# Gauge_DAC_v2.net
KiCad netlist of a schematic drawn in EAGLE
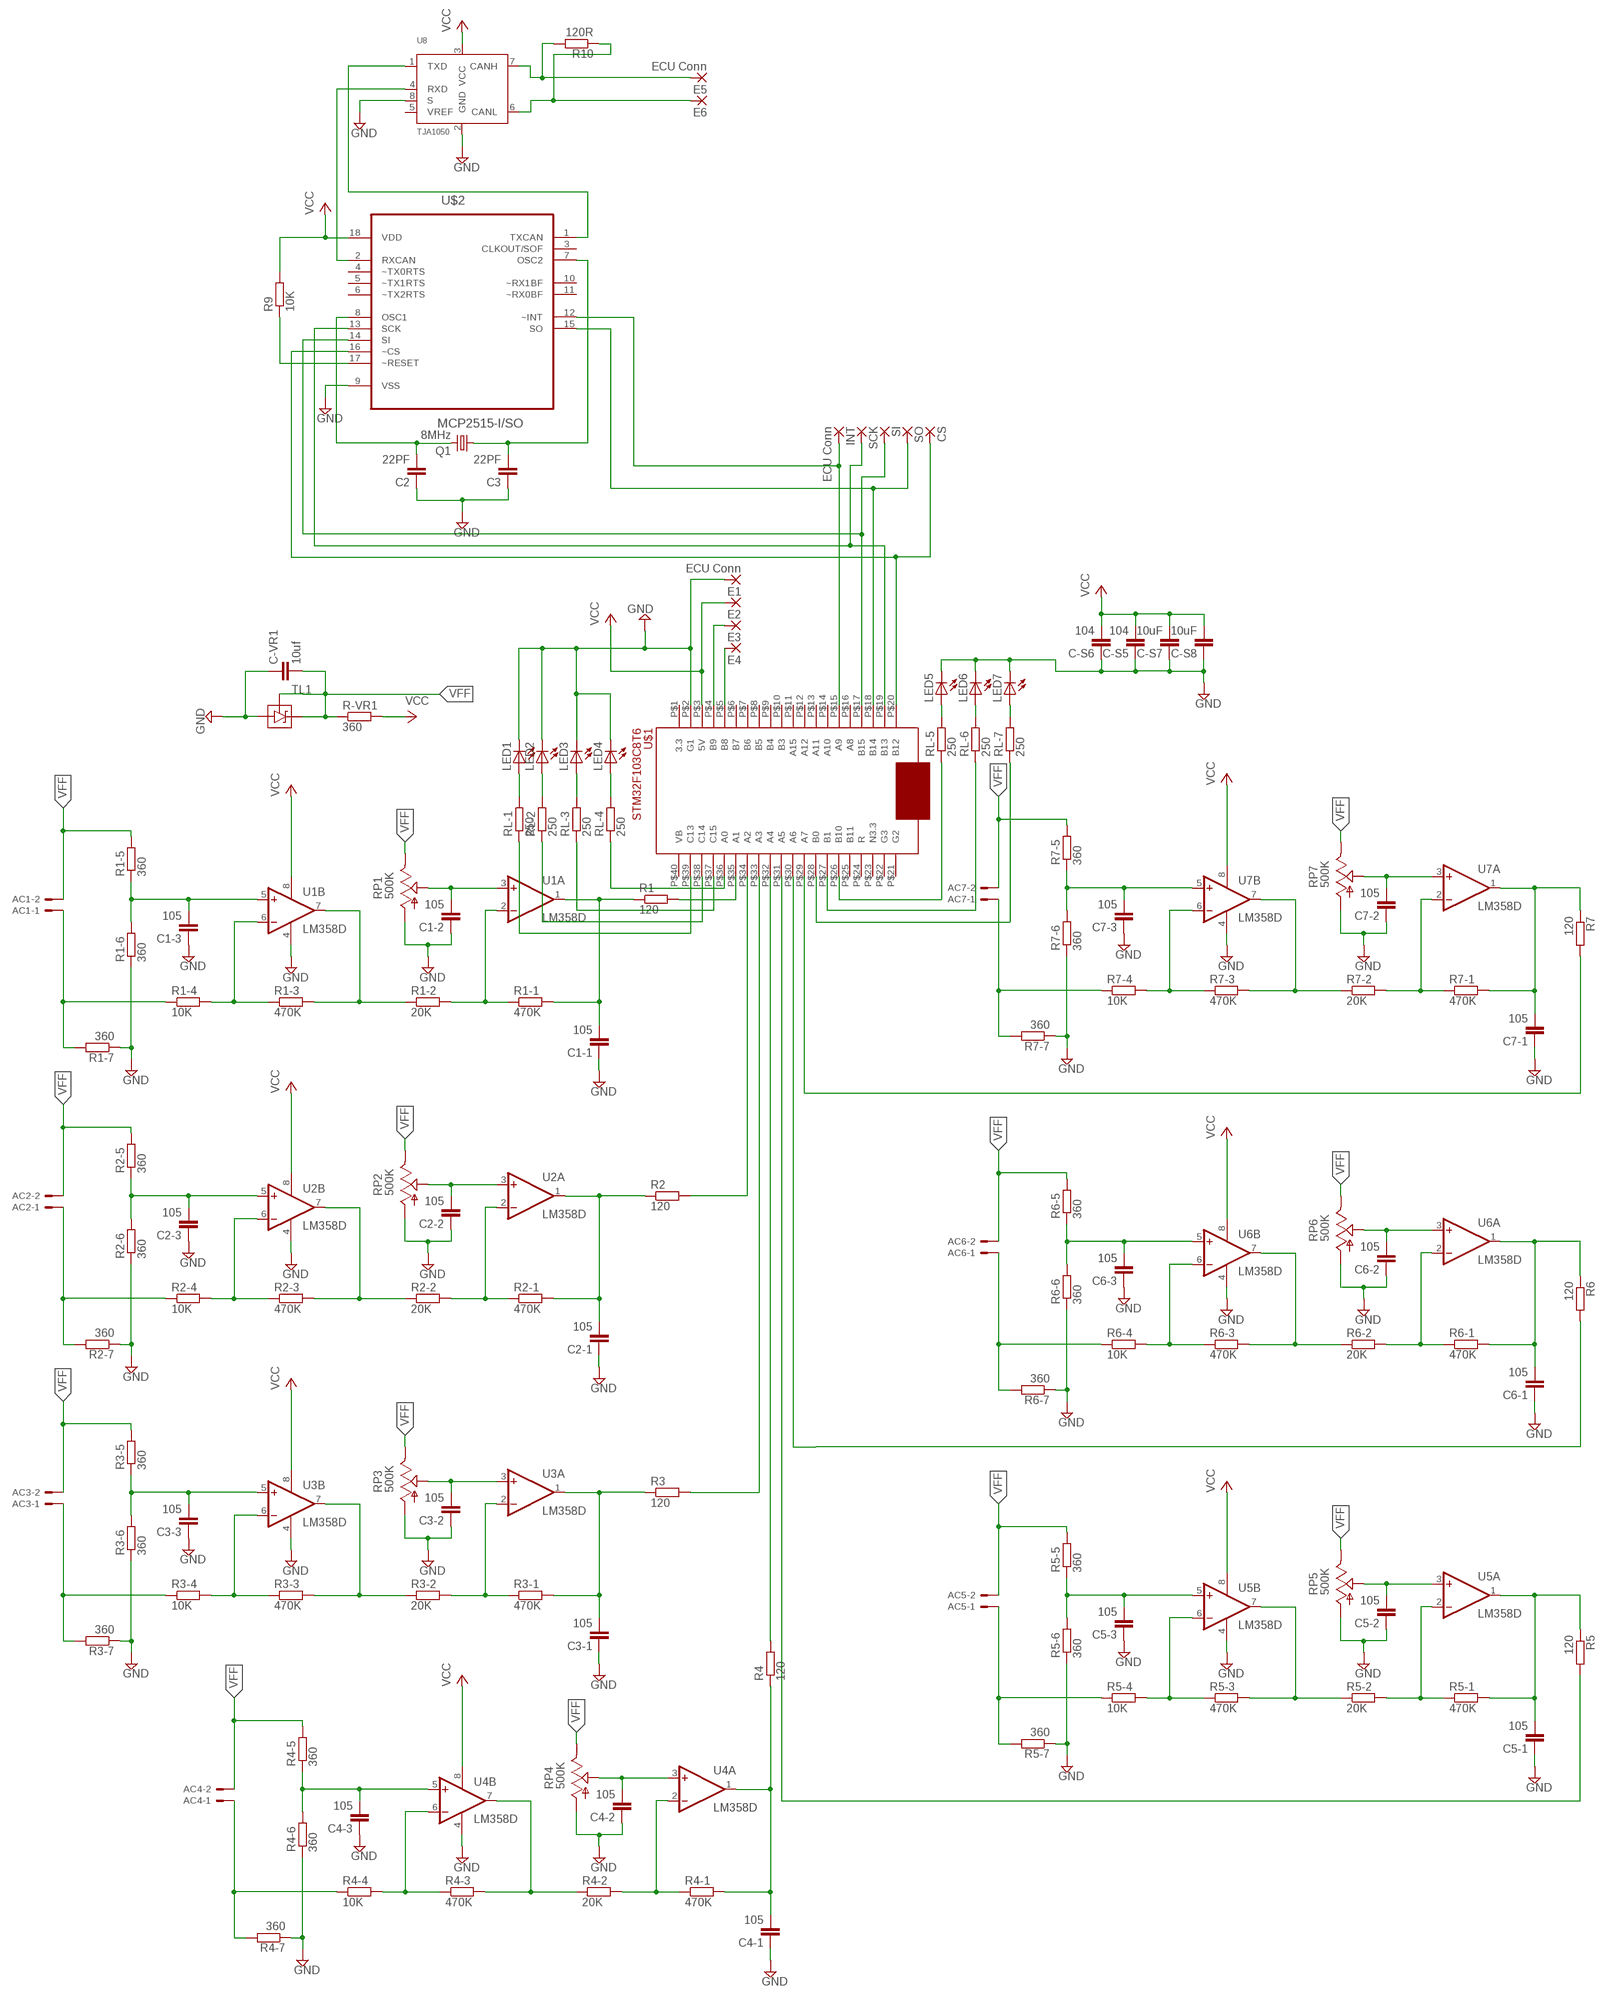
[diagram p0: schematic, sheet 1]

(export (version "E")
  (design (tool "Eeschema 10.0.6"))
  (components
    (comp (ref "AC1")
      (value "JST-XH-02-PIN-ROUND-PAD")
      (footprint "eagle-import:JST-XH-02-PACKAGE-ROUND-PAD")
      (libsource (lib "eagle-import") (part "JST-XH-02-PIN-ROUND-PAD"))
    )
    (comp (ref "AC2")
      (value "JST-XH-02-PIN-ROUND-PAD")
      (footprint "eagle-import:JST-XH-02-PACKAGE-ROUND-PAD")
      (libsource (lib "eagle-import") (part "JST-XH-02-PIN-ROUND-PAD"))
    )
    (comp (ref "AC3")
      (value "JST-XH-02-PIN-ROUND-PAD")
      (footprint "eagle-import:JST-XH-02-PACKAGE-ROUND-PAD")
      (libsource (lib "eagle-import") (part "JST-XH-02-PIN-ROUND-PAD"))
    )
    (comp (ref "AC4")
      (value "JST-XH-02-PIN-ROUND-PAD")
      (footprint "eagle-import:JST-XH-02-PACKAGE-ROUND-PAD")
      (libsource (lib "eagle-import") (part "JST-XH-02-PIN-ROUND-PAD"))
    )
    (comp (ref "AC5")
      (value "JST-XH-02-PIN-ROUND-PAD")
      (footprint "eagle-import:JST-XH-02-PACKAGE-ROUND-PAD")
      (libsource (lib "eagle-import") (part "JST-XH-02-PIN-ROUND-PAD"))
    )
    (comp (ref "AC6")
      (value "JST-XH-02-PIN-ROUND-PAD")
      (footprint "eagle-import:JST-XH-02-PACKAGE-ROUND-PAD")
      (libsource (lib "eagle-import") (part "JST-XH-02-PIN-ROUND-PAD"))
    )
    (comp (ref "AC7")
      (value "JST-XH-02-PIN-ROUND-PAD")
      (footprint "eagle-import:JST-XH-02-PACKAGE-ROUND-PAD")
      (libsource (lib "eagle-import") (part "JST-XH-02-PIN-ROUND-PAD"))
    )
    (comp (ref "C-S5")
      (value "104")
      (footprint "eagle-import:C0805")
      (libsource (lib "eagle-import") (part "C-EUC0805"))
    )
    (comp (ref "C-S6")
      (value "104")
      (footprint "eagle-import:C0805")
      (libsource (lib "eagle-import") (part "C-EUC0805"))
    )
    (comp (ref "C-S7")
      (value "10uF")
      (footprint "eagle-import:C0805")
      (libsource (lib "eagle-import") (part "C-EUC0805"))
    )
    (comp (ref "C-S8")
      (value "10uF")
      (footprint "eagle-import:C0805")
      (libsource (lib "eagle-import") (part "C-EUC0805"))
    )
    (comp (ref "C-VR1")
      (value "10uf")
      (footprint "eagle-import:C0805")
      (libsource (lib "eagle-import") (part "C-EUC0805"))
    )
    (comp (ref "C1-1")
      (value "105")
      (footprint "eagle-import:C0805")
      (libsource (lib "eagle-import") (part "C-EUC0805"))
    )
    (comp (ref "C1-2")
      (value "105")
      (footprint "eagle-import:C0805")
      (libsource (lib "eagle-import") (part "C-EUC0805"))
    )
    (comp (ref "C1-3")
      (value "105")
      (footprint "eagle-import:C0805")
      (libsource (lib "eagle-import") (part "C-EUC0805"))
    )
    (comp (ref "C2")
      (value "22PF")
      (footprint "eagle-import:C0805")
      (libsource (lib "eagle-import") (part "C-EUC0805"))
    )
    (comp (ref "C2-1")
      (value "105")
      (footprint "eagle-import:C0805")
      (libsource (lib "eagle-import") (part "C-EUC0805"))
    )
    (comp (ref "C2-2")
      (value "105")
      (footprint "eagle-import:C0805")
      (libsource (lib "eagle-import") (part "C-EUC0805"))
    )
    (comp (ref "C2-3")
      (value "105")
      (footprint "eagle-import:C0805")
      (libsource (lib "eagle-import") (part "C-EUC0805"))
    )
    (comp (ref "C3")
      (value "22PF")
      (footprint "eagle-import:C0805")
      (libsource (lib "eagle-import") (part "C-EUC0805"))
    )
    (comp (ref "C3-1")
      (value "105")
      (footprint "eagle-import:C0805")
      (libsource (lib "eagle-import") (part "C-EUC0805"))
    )
    (comp (ref "C3-2")
      (value "105")
      (footprint "eagle-import:C0805")
      (libsource (lib "eagle-import") (part "C-EUC0805"))
    )
    (comp (ref "C3-3")
      (value "105")
      (footprint "eagle-import:C0805")
      (libsource (lib "eagle-import") (part "C-EUC0805"))
    )
    (comp (ref "C4-1")
      (value "105")
      (footprint "eagle-import:C0805")
      (libsource (lib "eagle-import") (part "C-EUC0805"))
    )
    (comp (ref "C4-2")
      (value "105")
      (footprint "eagle-import:C0805")
      (libsource (lib "eagle-import") (part "C-EUC0805"))
    )
    (comp (ref "C4-3")
      (value "105")
      (footprint "eagle-import:C0805")
      (libsource (lib "eagle-import") (part "C-EUC0805"))
    )
    (comp (ref "C5-1")
      (value "105")
      (footprint "eagle-import:C0805")
      (libsource (lib "eagle-import") (part "C-EUC0805"))
    )
    (comp (ref "C5-2")
      (value "105")
      (footprint "eagle-import:C0805")
      (libsource (lib "eagle-import") (part "C-EUC0805"))
    )
    (comp (ref "C5-3")
      (value "105")
      (footprint "eagle-import:C0805")
      (libsource (lib "eagle-import") (part "C-EUC0805"))
    )
    (comp (ref "C6-1")
      (value "105")
      (footprint "eagle-import:C0805")
      (libsource (lib "eagle-import") (part "C-EUC0805"))
    )
    (comp (ref "C6-2")
      (value "105")
      (footprint "eagle-import:C0805")
      (libsource (lib "eagle-import") (part "C-EUC0805"))
    )
    (comp (ref "C6-3")
      (value "105")
      (footprint "eagle-import:C0805")
      (libsource (lib "eagle-import") (part "C-EUC0805"))
    )
    (comp (ref "C7-1")
      (value "105")
      (footprint "eagle-import:C0805")
      (libsource (lib "eagle-import") (part "C-EUC0805"))
    )
    (comp (ref "C7-2")
      (value "105")
      (footprint "eagle-import:C0805")
      (libsource (lib "eagle-import") (part "C-EUC0805"))
    )
    (comp (ref "C7-3")
      (value "105")
      (footprint "eagle-import:C0805")
      (libsource (lib "eagle-import") (part "C-EUC0805"))
    )
    (comp (ref "CS")
      (value "WIREPADSMD1,27-254")
      (footprint "eagle-import:SMD1,27-2,54")
      (libsource (lib "eagle-import") (part "WIREPADSMD1,27-254"))
    )
    (comp (ref "E1")
      (value "ECU Conn")
      (footprint "eagle-import:SMD1,27-2,54")
      (libsource (lib "eagle-import") (part "WIREPADSMD1,27-254"))
    )
    (comp (ref "E2")
      (value "WIREPADSMD1,27-254")
      (footprint "eagle-import:SMD1,27-2,54")
      (libsource (lib "eagle-import") (part "WIREPADSMD1,27-254"))
    )
    (comp (ref "E3")
      (value "WIREPADSMD1,27-254")
      (footprint "eagle-import:SMD1,27-2,54")
      (libsource (lib "eagle-import") (part "WIREPADSMD1,27-254"))
    )
    (comp (ref "E4")
      (value "WIREPADSMD1,27-254")
      (footprint "eagle-import:SMD1,27-2,54")
      (libsource (lib "eagle-import") (part "WIREPADSMD1,27-254"))
    )
    (comp (ref "E5")
      (value "ECU Conn")
      (footprint "eagle-import:SMD1,27-2,54")
      (libsource (lib "eagle-import") (part "WIREPADSMD1,27-254"))
    )
    (comp (ref "E6")
      (value "WIREPADSMD1,27-254")
      (footprint "eagle-import:SMD1,27-2,54")
      (libsource (lib "eagle-import") (part "WIREPADSMD1,27-254"))
    )
    (comp (ref "INT")
      (value "ECU Conn")
      (footprint "eagle-import:SMD1,27-2,54")
      (libsource (lib "eagle-import") (part "WIREPADSMD1,27-254"))
    )
    (comp (ref "LED1")
      (value "LEDCHIP-LED0805")
      (footprint "eagle-import:CHIP-LED0805")
      (libsource (lib "eagle-import") (part "LEDCHIP-LED0805"))
    )
    (comp (ref "LED2")
      (value "LEDCHIP-LED0805")
      (footprint "eagle-import:CHIP-LED0805")
      (libsource (lib "eagle-import") (part "LEDCHIP-LED0805"))
    )
    (comp (ref "LED3")
      (value "LEDCHIP-LED0805")
      (footprint "eagle-import:CHIP-LED0805")
      (libsource (lib "eagle-import") (part "LEDCHIP-LED0805"))
    )
    (comp (ref "LED4")
      (value "LEDCHIP-LED0805")
      (footprint "eagle-import:CHIP-LED0805")
      (libsource (lib "eagle-import") (part "LEDCHIP-LED0805"))
    )
    (comp (ref "LED5")
      (value "LEDCHIP-LED0805")
      (footprint "eagle-import:CHIP-LED0805")
      (libsource (lib "eagle-import") (part "LEDCHIP-LED0805"))
    )
    (comp (ref "LED6")
      (value "LEDCHIP-LED0805")
      (footprint "eagle-import:CHIP-LED0805")
      (libsource (lib "eagle-import") (part "LEDCHIP-LED0805"))
    )
    (comp (ref "LED7")
      (value "LEDCHIP-LED0805")
      (footprint "eagle-import:CHIP-LED0805")
      (libsource (lib "eagle-import") (part "LEDCHIP-LED0805"))
    )
    (comp (ref "Q1")
      (value "8MHz")
      (footprint "eagle-import:HC49_S")
      (libsource (lib "eagle-import") (part "CRYSTALHC49S"))
    )
    (comp (ref "R-VR1")
      (value "360")
      (footprint "eagle-import:M0805")
      (libsource (lib "eagle-import") (part "R-EU_M0805"))
    )
    (comp (ref "R1")
      (value "120")
      (footprint "eagle-import:M0805")
      (libsource (lib "eagle-import") (part "R-EU_M0805"))
    )
    (comp (ref "R1-1")
      (value "470K")
      (footprint "eagle-import:M0805")
      (libsource (lib "eagle-import") (part "R-EU_M0805"))
    )
    (comp (ref "R1-2")
      (value "20K")
      (footprint "eagle-import:M0805")
      (libsource (lib "eagle-import") (part "R-EU_M0805"))
    )
    (comp (ref "R1-3")
      (value "470K")
      (footprint "eagle-import:M0805")
      (libsource (lib "eagle-import") (part "R-EU_M0805"))
    )
    (comp (ref "R1-4")
      (value "10K")
      (footprint "eagle-import:M0805")
      (libsource (lib "eagle-import") (part "R-EU_M0805"))
    )
    (comp (ref "R1-5")
      (value "360")
      (footprint "eagle-import:M0805")
      (libsource (lib "eagle-import") (part "R-EU_M0805"))
    )
    (comp (ref "R1-6")
      (value "360")
      (footprint "eagle-import:M0805")
      (libsource (lib "eagle-import") (part "R-EU_M0805"))
    )
    (comp (ref "R1-7")
      (value "360")
      (footprint "eagle-import:M0805")
      (libsource (lib "eagle-import") (part "R-EU_M0805"))
    )
    (comp (ref "R2")
      (value "120")
      (footprint "eagle-import:M0805")
      (libsource (lib "eagle-import") (part "R-EU_M0805"))
    )
    (comp (ref "R2-1")
      (value "470K")
      (footprint "eagle-import:M0805")
      (libsource (lib "eagle-import") (part "R-EU_M0805"))
    )
    (comp (ref "R2-2")
      (value "20K")
      (footprint "eagle-import:M0805")
      (libsource (lib "eagle-import") (part "R-EU_M0805"))
    )
    (comp (ref "R2-3")
      (value "470K")
      (footprint "eagle-import:M0805")
      (libsource (lib "eagle-import") (part "R-EU_M0805"))
    )
    (comp (ref "R2-4")
      (value "10K")
      (footprint "eagle-import:M0805")
      (libsource (lib "eagle-import") (part "R-EU_M0805"))
    )
    (comp (ref "R2-5")
      (value "360")
      (footprint "eagle-import:M0805")
      (libsource (lib "eagle-import") (part "R-EU_M0805"))
    )
    (comp (ref "R2-6")
      (value "360")
      (footprint "eagle-import:M0805")
      (libsource (lib "eagle-import") (part "R-EU_M0805"))
    )
    (comp (ref "R2-7")
      (value "360")
      (footprint "eagle-import:M0805")
      (libsource (lib "eagle-import") (part "R-EU_M0805"))
    )
    (comp (ref "R3")
      (value "120")
      (footprint "eagle-import:M0805")
      (libsource (lib "eagle-import") (part "R-EU_M0805"))
    )
    (comp (ref "R3-1")
      (value "470K")
      (footprint "eagle-import:M0805")
      (libsource (lib "eagle-import") (part "R-EU_M0805"))
    )
    (comp (ref "R3-2")
      (value "20K")
      (footprint "eagle-import:M0805")
      (libsource (lib "eagle-import") (part "R-EU_M0805"))
    )
    (comp (ref "R3-3")
      (value "470K")
      (footprint "eagle-import:M0805")
      (libsource (lib "eagle-import") (part "R-EU_M0805"))
    )
    (comp (ref "R3-4")
      (value "10K")
      (footprint "eagle-import:M0805")
      (libsource (lib "eagle-import") (part "R-EU_M0805"))
    )
    (comp (ref "R3-5")
      (value "360")
      (footprint "eagle-import:M0805")
      (libsource (lib "eagle-import") (part "R-EU_M0805"))
    )
    (comp (ref "R3-6")
      (value "360")
      (footprint "eagle-import:M0805")
      (libsource (lib "eagle-import") (part "R-EU_M0805"))
    )
    (comp (ref "R3-7")
      (value "360")
      (footprint "eagle-import:M0805")
      (libsource (lib "eagle-import") (part "R-EU_M0805"))
    )
    (comp (ref "R4")
      (value "120")
      (footprint "eagle-import:M0805")
      (libsource (lib "eagle-import") (part "R-EU_M0805"))
    )
    (comp (ref "R4-1")
      (value "470K")
      (footprint "eagle-import:M0805")
      (libsource (lib "eagle-import") (part "R-EU_M0805"))
    )
    (comp (ref "R4-2")
      (value "20K")
      (footprint "eagle-import:M0805")
      (libsource (lib "eagle-import") (part "R-EU_M0805"))
    )
    (comp (ref "R4-3")
      (value "470K")
      (footprint "eagle-import:M0805")
      (libsource (lib "eagle-import") (part "R-EU_M0805"))
    )
    (comp (ref "R4-4")
      (value "10K")
      (footprint "eagle-import:M0805")
      (libsource (lib "eagle-import") (part "R-EU_M0805"))
    )
    (comp (ref "R4-5")
      (value "360")
      (footprint "eagle-import:M0805")
      (libsource (lib "eagle-import") (part "R-EU_M0805"))
    )
    (comp (ref "R4-6")
      (value "360")
      (footprint "eagle-import:M0805")
      (libsource (lib "eagle-import") (part "R-EU_M0805"))
    )
    (comp (ref "R4-7")
      (value "360")
      (footprint "eagle-import:M0805")
      (libsource (lib "eagle-import") (part "R-EU_M0805"))
    )
    (comp (ref "R5")
      (value "120")
      (footprint "eagle-import:M0805")
      (libsource (lib "eagle-import") (part "R-EU_M0805"))
    )
    (comp (ref "R5-1")
      (value "470K")
      (footprint "eagle-import:M0805")
      (libsource (lib "eagle-import") (part "R-EU_M0805"))
    )
    (comp (ref "R5-2")
      (value "20K")
      (footprint "eagle-import:M0805")
      (libsource (lib "eagle-import") (part "R-EU_M0805"))
    )
    (comp (ref "R5-3")
      (value "470K")
      (footprint "eagle-import:M0805")
      (libsource (lib "eagle-import") (part "R-EU_M0805"))
    )
    (comp (ref "R5-4")
      (value "10K")
      (footprint "eagle-import:M0805")
      (libsource (lib "eagle-import") (part "R-EU_M0805"))
    )
    (comp (ref "R5-5")
      (value "360")
      (footprint "eagle-import:M0805")
      (libsource (lib "eagle-import") (part "R-EU_M0805"))
    )
    (comp (ref "R5-6")
      (value "360")
      (footprint "eagle-import:M0805")
      (libsource (lib "eagle-import") (part "R-EU_M0805"))
    )
    (comp (ref "R5-7")
      (value "360")
      (footprint "eagle-import:M0805")
      (libsource (lib "eagle-import") (part "R-EU_M0805"))
    )
    (comp (ref "R6")
      (value "120")
      (footprint "eagle-import:M0805")
      (libsource (lib "eagle-import") (part "R-EU_M0805"))
    )
    (comp (ref "R6-1")
      (value "470K")
      (footprint "eagle-import:M0805")
      (libsource (lib "eagle-import") (part "R-EU_M0805"))
    )
    (comp (ref "R6-2")
      (value "20K")
      (footprint "eagle-import:M0805")
      (libsource (lib "eagle-import") (part "R-EU_M0805"))
    )
    (comp (ref "R6-3")
      (value "470K")
      (footprint "eagle-import:M0805")
      (libsource (lib "eagle-import") (part "R-EU_M0805"))
    )
    (comp (ref "R6-4")
      (value "10K")
      (footprint "eagle-import:M0805")
      (libsource (lib "eagle-import") (part "R-EU_M0805"))
    )
    (comp (ref "R6-5")
      (value "360")
      (footprint "eagle-import:M0805")
      (libsource (lib "eagle-import") (part "R-EU_M0805"))
    )
    (comp (ref "R6-6")
      (value "360")
      (footprint "eagle-import:M0805")
      (libsource (lib "eagle-import") (part "R-EU_M0805"))
    )
    (comp (ref "R6-7")
      (value "360")
      (footprint "eagle-import:M0805")
      (libsource (lib "eagle-import") (part "R-EU_M0805"))
    )
    (comp (ref "R7")
      (value "120")
      (footprint "eagle-import:M0805")
      (libsource (lib "eagle-import") (part "R-EU_M0805"))
    )
    (comp (ref "R7-1")
      (value "470K")
      (footprint "eagle-import:M0805")
      (libsource (lib "eagle-import") (part "R-EU_M0805"))
    )
    (comp (ref "R7-2")
      (value "20K")
      (footprint "eagle-import:M0805")
      (libsource (lib "eagle-import") (part "R-EU_M0805"))
    )
    (comp (ref "R7-3")
      (value "470K")
      (footprint "eagle-import:M0805")
      (libsource (lib "eagle-import") (part "R-EU_M0805"))
    )
    (comp (ref "R7-4")
      (value "10K")
      (footprint "eagle-import:M0805")
      (libsource (lib "eagle-import") (part "R-EU_M0805"))
    )
    (comp (ref "R7-5")
      (value "360")
      (footprint "eagle-import:M0805")
      (libsource (lib "eagle-import") (part "R-EU_M0805"))
    )
    (comp (ref "R7-6")
      (value "360")
      (footprint "eagle-import:M0805")
      (libsource (lib "eagle-import") (part "R-EU_M0805"))
    )
    (comp (ref "R7-7")
      (value "360")
      (footprint "eagle-import:M0805")
      (libsource (lib "eagle-import") (part "R-EU_M0805"))
    )
    (comp (ref "R9")
      (value "10K")
      (footprint "eagle-import:M0805")
      (libsource (lib "eagle-import") (part "R-EU_M0805"))
    )
    (comp (ref "R10")
      (value "120R")
      (footprint "eagle-import:M0805")
      (libsource (lib "eagle-import") (part "R-EU_M0805"))
    )
    (comp (ref "RL-1")
      (value "250")
      (footprint "eagle-import:M0805")
      (libsource (lib "eagle-import") (part "R-EU_M0805"))
    )
    (comp (ref "RL-2")
      (value "250")
      (footprint "eagle-import:M0805")
      (libsource (lib "eagle-import") (part "R-EU_M0805"))
    )
    (comp (ref "RL-3")
      (value "250")
      (footprint "eagle-import:M0805")
      (libsource (lib "eagle-import") (part "R-EU_M0805"))
    )
    (comp (ref "RL-4")
      (value "250")
      (footprint "eagle-import:M0805")
      (libsource (lib "eagle-import") (part "R-EU_M0805"))
    )
    (comp (ref "RL-5")
      (value "250")
      (footprint "eagle-import:M0805")
      (libsource (lib "eagle-import") (part "R-EU_M0805"))
    )
    (comp (ref "RL-6")
      (value "250")
      (footprint "eagle-import:M0805")
      (libsource (lib "eagle-import") (part "R-EU_M0805"))
    )
    (comp (ref "RL-7")
      (value "250")
      (footprint "eagle-import:M0805")
      (libsource (lib "eagle-import") (part "R-EU_M0805"))
    )
    (comp (ref "RP1")
      (value "500K")
      (footprint "eagle-import:B64Y")
      (fields (field (name "SPICEPREFIX") "J"))
      (libsource (lib "eagle-import") (part "TRIM_US-B64Y"))
    )
    (comp (ref "RP2")
      (value "500K")
      (footprint "eagle-import:B64Y")
      (fields (field (name "SPICEPREFIX") "J"))
      (libsource (lib "eagle-import") (part "TRIM_US-B64Y"))
    )
    (comp (ref "RP3")
      (value "500K")
      (footprint "eagle-import:B64Y")
      (fields (field (name "SPICEPREFIX") "J"))
      (libsource (lib "eagle-import") (part "TRIM_US-B64Y"))
    )
    (comp (ref "RP4")
      (value "500K")
      (footprint "eagle-import:B64Y")
      (fields (field (name "SPICEPREFIX") "J"))
      (libsource (lib "eagle-import") (part "TRIM_US-B64Y"))
    )
    (comp (ref "RP5")
      (value "500K")
      (footprint "eagle-import:B64Y")
      (fields (field (name "SPICEPREFIX") "J"))
      (libsource (lib "eagle-import") (part "TRIM_US-B64Y"))
    )
    (comp (ref "RP6")
      (value "500K")
      (footprint "eagle-import:B64Y")
      (fields (field (name "SPICEPREFIX") "J"))
      (libsource (lib "eagle-import") (part "TRIM_US-B64Y"))
    )
    (comp (ref "RP7")
      (value "500K")
      (footprint "eagle-import:B64Y")
      (fields (field (name "SPICEPREFIX") "J"))
      (libsource (lib "eagle-import") (part "TRIM_US-B64Y"))
    )
    (comp (ref "SCK")
      (value "WIREPADSMD1,27-254")
      (footprint "eagle-import:SMD1,27-2,54")
      (libsource (lib "eagle-import") (part "WIREPADSMD1,27-254"))
    )
    (comp (ref "SI")
      (value "WIREPADSMD1,27-254")
      (footprint "eagle-import:SMD1,27-2,54")
      (libsource (lib "eagle-import") (part "WIREPADSMD1,27-254"))
    )
    (comp (ref "SO")
      (value "WIREPADSMD1,27-254")
      (footprint "eagle-import:SMD1,27-2,54")
      (libsource (lib "eagle-import") (part "WIREPADSMD1,27-254"))
    )
    (comp (ref "TL1")
      (value "TL431SOT23")
      (footprint "eagle-import:SOT23")
      (libsource (lib "eagle-import") (part "TL431SOT23"))
    )
    (comp (ref "U$1")
      (value "STM32F103C8T6DIP40")
      (footprint "eagle-import:STM32")
      (libsource (lib "eagle-import") (part "STM32F103C8T6DIP40"))
    )
    (comp (ref "U$2")
      (value "MCP2515-I/SO")
      (footprint "eagle-import:SOIC127P1034X264-18N")
      (fields (field (name "MF") "Microchip"))
      (libsource (lib "eagle-import") (part "MCP2515-I/SO"))
    )
    (comp (ref "U1")
      (value "LM358D")
      (footprint "eagle-import:SO08")
      (fields (field (name "SPICEPREFIX") "J"))
      (libsource (lib "eagle-import") (part "LM358D"))
    )
    (comp (ref "U2")
      (value "LM358D")
      (footprint "eagle-import:SO08")
      (fields (field (name "SPICEPREFIX") "J"))
      (libsource (lib "eagle-import") (part "LM358D"))
    )
    (comp (ref "U3")
      (value "LM358D")
      (footprint "eagle-import:SO08")
      (fields (field (name "SPICEPREFIX") "J"))
      (libsource (lib "eagle-import") (part "LM358D"))
    )
    (comp (ref "U4")
      (value "LM358D")
      (footprint "eagle-import:SO08")
      (fields (field (name "SPICEPREFIX") "J"))
      (libsource (lib "eagle-import") (part "LM358D"))
    )
    (comp (ref "U5")
      (value "LM358D")
      (footprint "eagle-import:SO08")
      (fields (field (name "SPICEPREFIX") "J"))
      (libsource (lib "eagle-import") (part "LM358D"))
    )
    (comp (ref "U6")
      (value "LM358D")
      (footprint "eagle-import:SO08")
      (fields (field (name "SPICEPREFIX") "J"))
      (libsource (lib "eagle-import") (part "LM358D"))
    )
    (comp (ref "U7")
      (value "LM358D")
      (footprint "eagle-import:SO08")
      (fields (field (name "SPICEPREFIX") "J"))
      (libsource (lib "eagle-import") (part "LM358D"))
    )
    (comp (ref "U8")
      (value "TJA1050")
      (footprint "eagle-import:SOT96-1")
      (fields (field (name "MF") "NXP Semiconductors"))
      (libsource (lib "eagle-import") (part "TJA1050"))
    )
  )
  (nets
    (net (code "1") (name "GND") (class "Default")
      (node (ref "C-S5") (pin "1") (pinfunction "1_1") (pintype "passive"))
      (node (ref "C-S6") (pin "1") (pinfunction "1_1") (pintype "passive"))
      (node (ref "C-S7") (pin "1") (pinfunction "1_1") (pintype "passive"))
      (node (ref "C-S8") (pin "1") (pinfunction "1_1") (pintype "passive"))
      (node (ref "C-VR1") (pin "1") (pinfunction "1_1") (pintype "passive"))
      (node (ref "C1-1") (pin "1") (pinfunction "1_1") (pintype "passive"))
      (node (ref "C1-2") (pin "1") (pinfunction "1_1") (pintype "passive"))
      (node (ref "C1-3") (pin "1") (pinfunction "1_1") (pintype "passive"))
      (node (ref "C2") (pin "1") (pinfunction "1_1") (pintype "passive"))
      (node (ref "C2-1") (pin "1") (pinfunction "1_1") (pintype "passive"))
      (node (ref "C2-2") (pin "1") (pinfunction "1_1") (pintype "passive"))
      (node (ref "C2-3") (pin "1") (pinfunction "1_1") (pintype "passive"))
      (node (ref "C3") (pin "1") (pinfunction "1_1") (pintype "passive"))
      (node (ref "C3-1") (pin "1") (pinfunction "1_1") (pintype "passive"))
      (node (ref "C3-2") (pin "1") (pinfunction "1_1") (pintype "passive"))
      (node (ref "C3-3") (pin "1") (pinfunction "1_1") (pintype "passive"))
      (node (ref "C4-1") (pin "1") (pinfunction "1_1") (pintype "passive"))
      (node (ref "C4-2") (pin "1") (pinfunction "1_1") (pintype "passive"))
      (node (ref "C4-3") (pin "1") (pinfunction "1_1") (pintype "passive"))
      (node (ref "C5-1") (pin "1") (pinfunction "1_1") (pintype "passive"))
      (node (ref "C5-2") (pin "1") (pinfunction "1_1") (pintype "passive"))
      (node (ref "C5-3") (pin "1") (pinfunction "1_1") (pintype "passive"))
      (node (ref "C6-1") (pin "1") (pinfunction "1_1") (pintype "passive"))
      (node (ref "C6-2") (pin "1") (pinfunction "1_1") (pintype "passive"))
      (node (ref "C6-3") (pin "1") (pinfunction "1_1") (pintype "passive"))
      (node (ref "C7-1") (pin "1") (pinfunction "1_1") (pintype "passive"))
      (node (ref "C7-2") (pin "1") (pinfunction "1_1") (pintype "passive"))
      (node (ref "C7-3") (pin "1") (pinfunction "1_1") (pintype "passive"))
      (node (ref "E1") (pin "1") (pinfunction "P_1") (pintype "passive"))
      (node (ref "LED1") (pin "C") (pinfunction "C_C") (pintype "passive"))
      (node (ref "LED2") (pin "C") (pinfunction "C_C") (pintype "passive"))
      (node (ref "LED3") (pin "C") (pinfunction "C_C") (pintype "passive"))
      (node (ref "LED4") (pin "C") (pinfunction "C_C") (pintype "passive"))
      (node (ref "LED5") (pin "C") (pinfunction "C_C") (pintype "passive"))
      (node (ref "LED6") (pin "C") (pinfunction "C_C") (pintype "passive"))
      (node (ref "LED7") (pin "C") (pinfunction "C_C") (pintype "passive"))
      (node (ref "R1-6") (pin "1") (pinfunction "1_1") (pintype "passive"))
      (node (ref "R1-7") (pin "1") (pinfunction "1_1") (pintype "passive"))
      (node (ref "R2-6") (pin "1") (pinfunction "1_1") (pintype "passive"))
      (node (ref "R2-7") (pin "1") (pinfunction "1_1") (pintype "passive"))
      (node (ref "R3-6") (pin "1") (pinfunction "1_1") (pintype "passive"))
      (node (ref "R3-7") (pin "1") (pinfunction "1_1") (pintype "passive"))
      (node (ref "R4-6") (pin "1") (pinfunction "1_1") (pintype "passive"))
      (node (ref "R4-7") (pin "1") (pinfunction "1_1") (pintype "passive"))
      (node (ref "R5-6") (pin "1") (pinfunction "1_1") (pintype "passive"))
      (node (ref "R5-7") (pin "1") (pinfunction "1_1") (pintype "passive"))
      (node (ref "R6-6") (pin "1") (pinfunction "1_1") (pintype "passive"))
      (node (ref "R6-7") (pin "1") (pinfunction "1_1") (pintype "passive"))
      (node (ref "R7-6") (pin "1") (pinfunction "1_1") (pintype "passive"))
      (node (ref "R7-7") (pin "1") (pinfunction "1_1") (pintype "passive"))
      (node (ref "RP1") (pin "A") (pinfunction "A_A") (pintype "passive"))
      (node (ref "RP2") (pin "A") (pinfunction "A_A") (pintype "passive"))
      (node (ref "RP3") (pin "A") (pinfunction "A_A") (pintype "passive"))
      (node (ref "RP4") (pin "A") (pinfunction "A_A") (pintype "passive"))
      (node (ref "RP5") (pin "A") (pinfunction "A_A") (pintype "passive"))
      (node (ref "RP6") (pin "A") (pinfunction "A_A") (pintype "passive"))
      (node (ref "RP7") (pin "A") (pinfunction "A_A") (pintype "passive"))
      (node (ref "TL1") (pin "3") (pinfunction "ANODE_3") (pintype "bidirectional"))
      (node (ref "U$1") (pin "P$2") (pinfunction "G1_P$2") (pintype "bidirectional"))
      (node (ref "U$2") (pin "9") (pinfunction "VSS_9") (pintype "power_in"))
      (node (ref "U1") (pin "4") (pinfunction "V-_4") (pintype "power_in"))
      (node (ref "U2") (pin "4") (pinfunction "V-_4") (pintype "power_in"))
      (node (ref "U3") (pin "4") (pinfunction "V-_4") (pintype "power_in"))
      (node (ref "U4") (pin "4") (pinfunction "V-_4") (pintype "power_in"))
      (node (ref "U5") (pin "4") (pinfunction "V-_4") (pintype "power_in"))
      (node (ref "U6") (pin "4") (pinfunction "V-_4") (pintype "power_in"))
      (node (ref "U7") (pin "4") (pinfunction "V-_4") (pintype "power_in"))
      (node (ref "U8") (pin "2") (pinfunction "GND_2") (pintype "bidirectional"))
      (node (ref "U8") (pin "8") (pinfunction "S_8") (pintype "power_in"))
    )
    (net (code "2") (name "Net-(AC1A-S)") (class "Default")
      (node (ref "AC1") (pin "1") (pinfunction "S_1") (pintype "passive"))
      (node (ref "R1-4") (pin "1") (pinfunction "1_1") (pintype "passive"))
      (node (ref "R1-7") (pin "2") (pinfunction "2_2") (pintype "passive"))
    )
    (net (code "3") (name "Net-(AC2A-S)") (class "Default")
      (node (ref "AC2") (pin "1") (pinfunction "S_1") (pintype "passive"))
      (node (ref "R2-4") (pin "1") (pinfunction "1_1") (pintype "passive"))
      (node (ref "R2-7") (pin "2") (pinfunction "2_2") (pintype "passive"))
    )
    (net (code "4") (name "Net-(AC3A-S)") (class "Default")
      (node (ref "AC3") (pin "1") (pinfunction "S_1") (pintype "passive"))
      (node (ref "R3-4") (pin "1") (pinfunction "1_1") (pintype "passive"))
      (node (ref "R3-7") (pin "2") (pinfunction "2_2") (pintype "passive"))
    )
    (net (code "5") (name "Net-(AC4A-S)") (class "Default")
      (node (ref "AC4") (pin "1") (pinfunction "S_1") (pintype "passive"))
      (node (ref "R4-4") (pin "1") (pinfunction "1_1") (pintype "passive"))
      (node (ref "R4-7") (pin "2") (pinfunction "2_2") (pintype "passive"))
    )
    (net (code "6") (name "Net-(AC5A-S)") (class "Default")
      (node (ref "AC5") (pin "1") (pinfunction "S_1") (pintype "passive"))
      (node (ref "R5-4") (pin "1") (pinfunction "1_1") (pintype "passive"))
      (node (ref "R5-7") (pin "2") (pinfunction "2_2") (pintype "passive"))
    )
    (net (code "7") (name "Net-(AC6A-S)") (class "Default")
      (node (ref "AC6") (pin "1") (pinfunction "S_1") (pintype "passive"))
      (node (ref "R6-4") (pin "1") (pinfunction "1_1") (pintype "passive"))
      (node (ref "R6-7") (pin "2") (pinfunction "2_2") (pintype "passive"))
    )
    (net (code "8") (name "Net-(AC7A-S)") (class "Default")
      (node (ref "AC7") (pin "1") (pinfunction "S_1") (pintype "passive"))
      (node (ref "R7-4") (pin "1") (pinfunction "1_1") (pintype "passive"))
      (node (ref "R7-7") (pin "2") (pinfunction "2_2") (pintype "passive"))
    )
    (net (code "9") (name "Net-(CS-P)") (class "Default")
      (node (ref "CS") (pin "1") (pinfunction "P_1") (pintype "passive"))
      (node (ref "U$1") (pin "P$20") (pinfunction "B12_P$20") (pintype "bidirectional"))
      (node (ref "U$2") (pin "16") (pinfunction "~{CS}_16") (pintype "input"))
    )
    (net (code "10") (name "Net-(E3-P)") (class "Default")
      (node (ref "E3") (pin "1") (pinfunction "P_1") (pintype "passive"))
      (node (ref "U$1") (pin "P$4") (pinfunction "B9_P$4") (pintype "bidirectional"))
    )
    (net (code "11") (name "Net-(E4-P)") (class "Default")
      (node (ref "E4") (pin "1") (pinfunction "P_1") (pintype "passive"))
      (node (ref "U$1") (pin "P$5") (pinfunction "B8_P$5") (pintype "bidirectional"))
    )
    (net (code "12") (name "Net-(E5-P)") (class "Default")
      (node (ref "E5") (pin "1") (pinfunction "P_1") (pintype "passive"))
      (node (ref "R10") (pin "2") (pinfunction "2_2") (pintype "passive"))
      (node (ref "U8") (pin "7") (pinfunction "CANH_7") (pintype "bidirectional"))
    )
    (net (code "13") (name "Net-(E6-P)") (class "Default")
      (node (ref "E6") (pin "1") (pinfunction "P_1") (pintype "passive"))
      (node (ref "R10") (pin "1") (pinfunction "1_1") (pintype "passive"))
      (node (ref "U8") (pin "6") (pinfunction "CANL_6") (pintype "bidirectional"))
    )
    (net (code "14") (name "Net-(INT-P)") (class "Default")
      (node (ref "INT") (pin "1") (pinfunction "P_1") (pintype "passive"))
      (node (ref "U$1") (pin "P$15") (pinfunction "A9_P$15") (pintype "bidirectional"))
      (node (ref "U$2") (pin "12") (pinfunction "~{INT}_12") (pintype "output"))
    )
    (net (code "15") (name "Net-(LED1-PadA)") (class "Default")
      (node (ref "LED1") (pin "A") (pinfunction "A_A") (pintype "passive"))
      (node (ref "RL-1") (pin "2") (pinfunction "2_2") (pintype "passive"))
    )
    (net (code "16") (name "Net-(LED2-PadA)") (class "Default")
      (node (ref "LED2") (pin "A") (pinfunction "A_A") (pintype "passive"))
      (node (ref "RL-2") (pin "2") (pinfunction "2_2") (pintype "passive"))
    )
    (net (code "17") (name "Net-(LED3-PadA)") (class "Default")
      (node (ref "LED3") (pin "A") (pinfunction "A_A") (pintype "passive"))
      (node (ref "RL-3") (pin "2") (pinfunction "2_2") (pintype "passive"))
    )
    (net (code "18") (name "Net-(LED4-PadA)") (class "Default")
      (node (ref "LED4") (pin "A") (pinfunction "A_A") (pintype "passive"))
      (node (ref "RL-4") (pin "2") (pinfunction "2_2") (pintype "passive"))
    )
    (net (code "19") (name "Net-(LED5-PadA)") (class "Default")
      (node (ref "LED5") (pin "A") (pinfunction "A_A") (pintype "passive"))
      (node (ref "RL-5") (pin "2") (pinfunction "2_2") (pintype "passive"))
    )
    (net (code "20") (name "Net-(LED6-PadA)") (class "Default")
      (node (ref "LED6") (pin "A") (pinfunction "A_A") (pintype "passive"))
      (node (ref "RL-6") (pin "2") (pinfunction "2_2") (pintype "passive"))
    )
    (net (code "21") (name "Net-(LED7-PadA)") (class "Default")
      (node (ref "LED7") (pin "A") (pinfunction "A_A") (pintype "passive"))
      (node (ref "RL-7") (pin "2") (pinfunction "2_2") (pintype "passive"))
    )
    (net (code "22") (name "Net-(SCK-P)") (class "Default")
      (node (ref "SCK") (pin "1") (pinfunction "P_1") (pintype "passive"))
      (node (ref "U$1") (pin "P$19") (pinfunction "B13_P$19") (pintype "bidirectional"))
      (node (ref "U$2") (pin "13") (pinfunction "SCK_13") (pintype "input"))
    )
    (net (code "23") (name "Net-(SI-P)") (class "Default")
      (node (ref "SI") (pin "1") (pinfunction "P_1") (pintype "passive"))
      (node (ref "U$1") (pin "P$17") (pinfunction "B15_P$17") (pintype "bidirectional"))
      (node (ref "U$2") (pin "14") (pinfunction "SI_14") (pintype "input"))
    )
    (net (code "24") (name "Net-(SO-P)") (class "Default")
      (node (ref "SO") (pin "1") (pinfunction "P_1") (pintype "passive"))
      (node (ref "U$1") (pin "P$18") (pinfunction "B14_P$18") (pintype "bidirectional"))
      (node (ref "U$2") (pin "15") (pinfunction "SO_15") (pintype "output"))
    )
    (net (code "25") (name "Net-(U$1-A0)") (class "Default")
      (node (ref "RL-4") (pin "1") (pinfunction "1_1") (pintype "passive"))
      (node (ref "U$1") (pin "P$36") (pinfunction "A0_P$36") (pintype "bidirectional"))
    )
    (net (code "26") (name "Net-(U$1-A1)") (class "Default")
      (node (ref "R1") (pin "2") (pinfunction "2_2") (pintype "passive"))
      (node (ref "U$1") (pin "P$35") (pinfunction "A1_P$35") (pintype "bidirectional"))
    )
    (net (code "27") (name "Net-(U$1-A2)") (class "Default")
      (node (ref "R2") (pin "2") (pinfunction "2_2") (pintype "passive"))
      (node (ref "U$1") (pin "P$34") (pinfunction "A2_P$34") (pintype "bidirectional"))
    )
    (net (code "28") (name "Net-(U$1-A3)") (class "Default")
      (node (ref "R3") (pin "2") (pinfunction "2_2") (pintype "passive"))
      (node (ref "U$1") (pin "P$33") (pinfunction "A3_P$33") (pintype "bidirectional"))
    )
    (net (code "29") (name "Net-(U$1-A4)") (class "Default")
      (node (ref "R4") (pin "2") (pinfunction "2_2") (pintype "passive"))
      (node (ref "U$1") (pin "P$32") (pinfunction "A4_P$32") (pintype "bidirectional"))
    )
    (net (code "30") (name "Net-(U$1-A5)") (class "Default")
      (node (ref "R5") (pin "2") (pinfunction "2_2") (pintype "passive"))
      (node (ref "U$1") (pin "P$31") (pinfunction "A5_P$31") (pintype "bidirectional"))
    )
    (net (code "31") (name "Net-(U$1-A6)") (class "Default")
      (node (ref "R6") (pin "2") (pinfunction "2_2") (pintype "passive"))
      (node (ref "U$1") (pin "P$30") (pinfunction "A6_P$30") (pintype "bidirectional"))
    )
    (net (code "32") (name "Net-(U$1-A7)") (class "Default")
      (node (ref "R7") (pin "2") (pinfunction "2_2") (pintype "passive"))
      (node (ref "U$1") (pin "P$29") (pinfunction "A7_P$29") (pintype "bidirectional"))
    )
    (net (code "33") (name "Net-(U$1-B0)") (class "Default")
      (node (ref "RL-7") (pin "1") (pinfunction "1_1") (pintype "passive"))
      (node (ref "U$1") (pin "P$28") (pinfunction "B0_P$28") (pintype "bidirectional"))
    )
    (net (code "34") (name "Net-(U$1-B1)") (class "Default")
      (node (ref "RL-6") (pin "1") (pinfunction "1_1") (pintype "passive"))
      (node (ref "U$1") (pin "P$27") (pinfunction "B1_P$27") (pintype "bidirectional"))
    )
    (net (code "35") (name "Net-(U$1-B10)") (class "Default")
      (node (ref "RL-5") (pin "1") (pinfunction "1_1") (pintype "passive"))
      (node (ref "U$1") (pin "P$26") (pinfunction "B10_P$26") (pintype "bidirectional"))
    )
    (net (code "36") (name "Net-(U$1-C13)") (class "Default")
      (node (ref "RL-1") (pin "1") (pinfunction "1_1") (pintype "passive"))
      (node (ref "U$1") (pin "P$39") (pinfunction "C13_P$39") (pintype "bidirectional"))
    )
    (net (code "37") (name "Net-(U$1-C14)") (class "Default")
      (node (ref "RL-2") (pin "1") (pinfunction "1_1") (pintype "passive"))
      (node (ref "U$1") (pin "P$38") (pinfunction "C14_P$38") (pintype "bidirectional"))
    )
    (net (code "38") (name "Net-(U$1-C15)") (class "Default")
      (node (ref "RL-3") (pin "1") (pinfunction "1_1") (pintype "passive"))
      (node (ref "U$1") (pin "P$37") (pinfunction "C15_P$37") (pintype "bidirectional"))
    )
    (net (code "39") (name "Net-(U$2-OSC1)") (class "Default")
      (node (ref "C2") (pin "2") (pinfunction "2_2") (pintype "passive"))
      (node (ref "Q1") (pin "2") (pinfunction "2_2") (pintype "passive"))
      (node (ref "U$2") (pin "8") (pinfunction "OSC1_8") (pintype "input"))
    )
    (net (code "40") (name "Net-(U$2-OSC2)") (class "Default")
      (node (ref "C3") (pin "2") (pinfunction "2_2") (pintype "passive"))
      (node (ref "Q1") (pin "1") (pinfunction "1_1") (pintype "passive"))
      (node (ref "U$2") (pin "7") (pinfunction "OSC2_7") (pintype "output"))
    )
    (net (code "41") (name "Net-(U$2-RXCAN)") (class "Default")
      (node (ref "U$2") (pin "2") (pinfunction "RXCAN_2") (pintype "input"))
      (node (ref "U8") (pin "4") (pinfunction "RXD_4") (pintype "bidirectional"))
    )
    (net (code "42") (name "Net-(U$2-TXCAN)") (class "Default")
      (node (ref "U$2") (pin "1") (pinfunction "TXCAN_1") (pintype "output"))
      (node (ref "U8") (pin "1") (pinfunction "TXD_1") (pintype "output"))
    )
    (net (code "43") (name "Net-(U$2-~{RESET})") (class "Default")
      (node (ref "R9") (pin "1") (pinfunction "1_1") (pintype "passive"))
      (node (ref "U$2") (pin "17") (pinfunction "~{RESET}_17") (pintype "input"))
    )
    (net (code "44") (name "Net-(U1A-+IN)") (class "Default")
      (node (ref "C1-2") (pin "2") (pinfunction "2_2") (pintype "passive"))
      (node (ref "RP1") (pin "S") (pinfunction "S_S") (pintype "passive"))
      (node (ref "U1") (pin "3") (pinfunction "+IN_3") (pintype "input"))
    )
    (net (code "45") (name "Net-(U1A--IN)") (class "Default")
      (node (ref "R1-1") (pin "1") (pinfunction "1_1") (pintype "passive"))
      (node (ref "R1-2") (pin "2") (pinfunction "2_2") (pintype "passive"))
      (node (ref "U1") (pin "2") (pinfunction "-IN_2") (pintype "input"))
    )
    (net (code "46") (name "Net-(U1A-OUT)") (class "Default")
      (node (ref "C1-1") (pin "2") (pinfunction "2_2") (pintype "passive"))
      (node (ref "R1") (pin "1") (pinfunction "1_1") (pintype "passive"))
      (node (ref "R1-1") (pin "2") (pinfunction "2_2") (pintype "passive"))
      (node (ref "U1") (pin "1") (pinfunction "OUT_1") (pintype "output"))
    )
    (net (code "47") (name "Net-(U1B-+IN)") (class "Default")
      (node (ref "C1-3") (pin "2") (pinfunction "2_2") (pintype "passive"))
      (node (ref "R1-5") (pin "1") (pinfunction "1_1") (pintype "passive"))
      (node (ref "R1-6") (pin "2") (pinfunction "2_2") (pintype "passive"))
      (node (ref "U1") (pin "5") (pinfunction "+IN_5") (pintype "input"))
    )
    (net (code "48") (name "Net-(U1B--IN)") (class "Default")
      (node (ref "R1-3") (pin "1") (pinfunction "1_1") (pintype "passive"))
      (node (ref "R1-4") (pin "2") (pinfunction "2_2") (pintype "passive"))
      (node (ref "U1") (pin "6") (pinfunction "-IN_6") (pintype "input"))
    )
    (net (code "49") (name "Net-(U1B-OUT)") (class "Default")
      (node (ref "R1-2") (pin "1") (pinfunction "1_1") (pintype "passive"))
      (node (ref "R1-3") (pin "2") (pinfunction "2_2") (pintype "passive"))
      (node (ref "U1") (pin "7") (pinfunction "OUT_7") (pintype "output"))
    )
    (net (code "50") (name "Net-(U2A-+IN)") (class "Default")
      (node (ref "C2-2") (pin "2") (pinfunction "2_2") (pintype "passive"))
      (node (ref "RP2") (pin "S") (pinfunction "S_S") (pintype "passive"))
      (node (ref "U2") (pin "3") (pinfunction "+IN_3") (pintype "input"))
    )
    (net (code "51") (name "Net-(U2A--IN)") (class "Default")
      (node (ref "R2-1") (pin "1") (pinfunction "1_1") (pintype "passive"))
      (node (ref "R2-2") (pin "2") (pinfunction "2_2") (pintype "passive"))
      (node (ref "U2") (pin "2") (pinfunction "-IN_2") (pintype "input"))
    )
    (net (code "52") (name "Net-(U2A-OUT)") (class "Default")
      (node (ref "C2-1") (pin "2") (pinfunction "2_2") (pintype "passive"))
      (node (ref "R2") (pin "1") (pinfunction "1_1") (pintype "passive"))
      (node (ref "R2-1") (pin "2") (pinfunction "2_2") (pintype "passive"))
      (node (ref "U2") (pin "1") (pinfunction "OUT_1") (pintype "output"))
    )
    (net (code "53") (name "Net-(U2B-+IN)") (class "Default")
      (node (ref "C2-3") (pin "2") (pinfunction "2_2") (pintype "passive"))
      (node (ref "R2-5") (pin "1") (pinfunction "1_1") (pintype "passive"))
      (node (ref "R2-6") (pin "2") (pinfunction "2_2") (pintype "passive"))
      (node (ref "U2") (pin "5") (pinfunction "+IN_5") (pintype "input"))
    )
    (net (code "54") (name "Net-(U2B--IN)") (class "Default")
      (node (ref "R2-3") (pin "1") (pinfunction "1_1") (pintype "passive"))
      (node (ref "R2-4") (pin "2") (pinfunction "2_2") (pintype "passive"))
      (node (ref "U2") (pin "6") (pinfunction "-IN_6") (pintype "input"))
    )
    (net (code "55") (name "Net-(U2B-OUT)") (class "Default")
      (node (ref "R2-2") (pin "1") (pinfunction "1_1") (pintype "passive"))
      (node (ref "R2-3") (pin "2") (pinfunction "2_2") (pintype "passive"))
      (node (ref "U2") (pin "7") (pinfunction "OUT_7") (pintype "output"))
    )
    (net (code "56") (name "Net-(U3A-+IN)") (class "Default")
      (node (ref "C3-2") (pin "2") (pinfunction "2_2") (pintype "passive"))
      (node (ref "RP3") (pin "S") (pinfunction "S_S") (pintype "passive"))
      (node (ref "U3") (pin "3") (pinfunction "+IN_3") (pintype "input"))
    )
    (net (code "57") (name "Net-(U3A--IN)") (class "Default")
      (node (ref "R3-1") (pin "1") (pinfunction "1_1") (pintype "passive"))
      (node (ref "R3-2") (pin "2") (pinfunction "2_2") (pintype "passive"))
      (node (ref "U3") (pin "2") (pinfunction "-IN_2") (pintype "input"))
    )
    (net (code "58") (name "Net-(U3A-OUT)") (class "Default")
      (node (ref "C3-1") (pin "2") (pinfunction "2_2") (pintype "passive"))
      (node (ref "R3") (pin "1") (pinfunction "1_1") (pintype "passive"))
      (node (ref "R3-1") (pin "2") (pinfunction "2_2") (pintype "passive"))
      (node (ref "U3") (pin "1") (pinfunction "OUT_1") (pintype "output"))
    )
    (net (code "59") (name "Net-(U3B-+IN)") (class "Default")
      (node (ref "C3-3") (pin "2") (pinfunction "2_2") (pintype "passive"))
      (node (ref "R3-5") (pin "1") (pinfunction "1_1") (pintype "passive"))
      (node (ref "R3-6") (pin "2") (pinfunction "2_2") (pintype "passive"))
      (node (ref "U3") (pin "5") (pinfunction "+IN_5") (pintype "input"))
    )
    (net (code "60") (name "Net-(U3B--IN)") (class "Default")
      (node (ref "R3-3") (pin "1") (pinfunction "1_1") (pintype "passive"))
      (node (ref "R3-4") (pin "2") (pinfunction "2_2") (pintype "passive"))
      (node (ref "U3") (pin "6") (pinfunction "-IN_6") (pintype "input"))
    )
    (net (code "61") (name "Net-(U3B-OUT)") (class "Default")
      (node (ref "R3-2") (pin "1") (pinfunction "1_1") (pintype "passive"))
      (node (ref "R3-3") (pin "2") (pinfunction "2_2") (pintype "passive"))
      (node (ref "U3") (pin "7") (pinfunction "OUT_7") (pintype "output"))
    )
    (net (code "62") (name "Net-(U4A-+IN)") (class "Default")
      (node (ref "C4-2") (pin "2") (pinfunction "2_2") (pintype "passive"))
      (node (ref "RP4") (pin "S") (pinfunction "S_S") (pintype "passive"))
      (node (ref "U4") (pin "3") (pinfunction "+IN_3") (pintype "input"))
    )
    (net (code "63") (name "Net-(U4A--IN)") (class "Default")
      (node (ref "R4-1") (pin "1") (pinfunction "1_1") (pintype "passive"))
      (node (ref "R4-2") (pin "2") (pinfunction "2_2") (pintype "passive"))
      (node (ref "U4") (pin "2") (pinfunction "-IN_2") (pintype "input"))
    )
    (net (code "64") (name "Net-(U4A-OUT)") (class "Default")
      (node (ref "C4-1") (pin "2") (pinfunction "2_2") (pintype "passive"))
      (node (ref "R4") (pin "1") (pinfunction "1_1") (pintype "passive"))
      (node (ref "R4-1") (pin "2") (pinfunction "2_2") (pintype "passive"))
      (node (ref "U4") (pin "1") (pinfunction "OUT_1") (pintype "output"))
    )
    (net (code "65") (name "Net-(U4B-+IN)") (class "Default")
      (node (ref "C4-3") (pin "2") (pinfunction "2_2") (pintype "passive"))
      (node (ref "R4-5") (pin "1") (pinfunction "1_1") (pintype "passive"))
      (node (ref "R4-6") (pin "2") (pinfunction "2_2") (pintype "passive"))
      (node (ref "U4") (pin "5") (pinfunction "+IN_5") (pintype "input"))
    )
    (net (code "66") (name "Net-(U4B--IN)") (class "Default")
      (node (ref "R4-3") (pin "1") (pinfunction "1_1") (pintype "passive"))
      (node (ref "R4-4") (pin "2") (pinfunction "2_2") (pintype "passive"))
      (node (ref "U4") (pin "6") (pinfunction "-IN_6") (pintype "input"))
    )
    (net (code "67") (name "Net-(U4B-OUT)") (class "Default")
      (node (ref "R4-2") (pin "1") (pinfunction "1_1") (pintype "passive"))
      (node (ref "R4-3") (pin "2") (pinfunction "2_2") (pintype "passive"))
      (node (ref "U4") (pin "7") (pinfunction "OUT_7") (pintype "output"))
    )
    (net (code "68") (name "Net-(U5A-+IN)") (class "Default")
      (node (ref "C5-2") (pin "2") (pinfunction "2_2") (pintype "passive"))
      (node (ref "RP5") (pin "S") (pinfunction "S_S") (pintype "passive"))
      (node (ref "U5") (pin "3") (pinfunction "+IN_3") (pintype "input"))
    )
    (net (code "69") (name "Net-(U5A--IN)") (class "Default")
      (node (ref "R5-1") (pin "1") (pinfunction "1_1") (pintype "passive"))
      (node (ref "R5-2") (pin "2") (pinfunction "2_2") (pintype "passive"))
      (node (ref "U5") (pin "2") (pinfunction "-IN_2") (pintype "input"))
    )
    (net (code "70") (name "Net-(U5A-OUT)") (class "Default")
      (node (ref "C5-1") (pin "2") (pinfunction "2_2") (pintype "passive"))
      (node (ref "R5") (pin "1") (pinfunction "1_1") (pintype "passive"))
      (node (ref "R5-1") (pin "2") (pinfunction "2_2") (pintype "passive"))
      (node (ref "U5") (pin "1") (pinfunction "OUT_1") (pintype "output"))
    )
    (net (code "71") (name "Net-(U5B-+IN)") (class "Default")
      (node (ref "C5-3") (pin "2") (pinfunction "2_2") (pintype "passive"))
      (node (ref "R5-5") (pin "1") (pinfunction "1_1") (pintype "passive"))
      (node (ref "R5-6") (pin "2") (pinfunction "2_2") (pintype "passive"))
      (node (ref "U5") (pin "5") (pinfunction "+IN_5") (pintype "input"))
    )
    (net (code "72") (name "Net-(U5B--IN)") (class "Default")
      (node (ref "R5-3") (pin "1") (pinfunction "1_1") (pintype "passive"))
      (node (ref "R5-4") (pin "2") (pinfunction "2_2") (pintype "passive"))
      (node (ref "U5") (pin "6") (pinfunction "-IN_6") (pintype "input"))
    )
    (net (code "73") (name "Net-(U5B-OUT)") (class "Default")
      (node (ref "R5-2") (pin "1") (pinfunction "1_1") (pintype "passive"))
      (node (ref "R5-3") (pin "2") (pinfunction "2_2") (pintype "passive"))
      (node (ref "U5") (pin "7") (pinfunction "OUT_7") (pintype "output"))
    )
    (net (code "74") (name "Net-(U6A-+IN)") (class "Default")
      (node (ref "C6-2") (pin "2") (pinfunction "2_2") (pintype "passive"))
      (node (ref "RP6") (pin "S") (pinfunction "S_S") (pintype "passive"))
      (node (ref "U6") (pin "3") (pinfunction "+IN_3") (pintype "input"))
    )
    (net (code "75") (name "Net-(U6A--IN)") (class "Default")
      (node (ref "R6-1") (pin "1") (pinfunction "1_1") (pintype "passive"))
      (node (ref "R6-2") (pin "2") (pinfunction "2_2") (pintype "passive"))
      (node (ref "U6") (pin "2") (pinfunction "-IN_2") (pintype "input"))
    )
    (net (code "76") (name "Net-(U6A-OUT)") (class "Default")
      (node (ref "C6-1") (pin "2") (pinfunction "2_2") (pintype "passive"))
      (node (ref "R6") (pin "1") (pinfunction "1_1") (pintype "passive"))
      (node (ref "R6-1") (pin "2") (pinfunction "2_2") (pintype "passive"))
      (node (ref "U6") (pin "1") (pinfunction "OUT_1") (pintype "output"))
    )
    (net (code "77") (name "Net-(U6B-+IN)") (class "Default")
      (node (ref "C6-3") (pin "2") (pinfunction "2_2") (pintype "passive"))
      (node (ref "R6-5") (pin "1") (pinfunction "1_1") (pintype "passive"))
      (node (ref "R6-6") (pin "2") (pinfunction "2_2") (pintype "passive"))
      (node (ref "U6") (pin "5") (pinfunction "+IN_5") (pintype "input"))
    )
    (net (code "78") (name "Net-(U6B--IN)") (class "Default")
      (node (ref "R6-3") (pin "1") (pinfunction "1_1") (pintype "passive"))
      (node (ref "R6-4") (pin "2") (pinfunction "2_2") (pintype "passive"))
      (node (ref "U6") (pin "6") (pinfunction "-IN_6") (pintype "input"))
    )
    (net (code "79") (name "Net-(U6B-OUT)") (class "Default")
      (node (ref "R6-2") (pin "1") (pinfunction "1_1") (pintype "passive"))
      (node (ref "R6-3") (pin "2") (pinfunction "2_2") (pintype "passive"))
      (node (ref "U6") (pin "7") (pinfunction "OUT_7") (pintype "output"))
    )
    (net (code "80") (name "Net-(U7A-+IN)") (class "Default")
      (node (ref "C7-2") (pin "2") (pinfunction "2_2") (pintype "passive"))
      (node (ref "RP7") (pin "S") (pinfunction "S_S") (pintype "passive"))
      (node (ref "U7") (pin "3") (pinfunction "+IN_3") (pintype "input"))
    )
    (net (code "81") (name "Net-(U7A--IN)") (class "Default")
      (node (ref "R7-1") (pin "1") (pinfunction "1_1") (pintype "passive"))
      (node (ref "R7-2") (pin "2") (pinfunction "2_2") (pintype "passive"))
      (node (ref "U7") (pin "2") (pinfunction "-IN_2") (pintype "input"))
    )
    (net (code "82") (name "Net-(U7A-OUT)") (class "Default")
      (node (ref "C7-1") (pin "2") (pinfunction "2_2") (pintype "passive"))
      (node (ref "R7") (pin "1") (pinfunction "1_1") (pintype "passive"))
      (node (ref "R7-1") (pin "2") (pinfunction "2_2") (pintype "passive"))
      (node (ref "U7") (pin "1") (pinfunction "OUT_1") (pintype "output"))
    )
    (net (code "83") (name "Net-(U7B-+IN)") (class "Default")
      (node (ref "C7-3") (pin "2") (pinfunction "2_2") (pintype "passive"))
      (node (ref "R7-5") (pin "1") (pinfunction "1_1") (pintype "passive"))
      (node (ref "R7-6") (pin "2") (pinfunction "2_2") (pintype "passive"))
      (node (ref "U7") (pin "5") (pinfunction "+IN_5") (pintype "input"))
    )
    (net (code "84") (name "Net-(U7B--IN)") (class "Default")
      (node (ref "R7-3") (pin "1") (pinfunction "1_1") (pintype "passive"))
      (node (ref "R7-4") (pin "2") (pinfunction "2_2") (pintype "passive"))
      (node (ref "U7") (pin "6") (pinfunction "-IN_6") (pintype "input"))
    )
    (net (code "85") (name "Net-(U7B-OUT)") (class "Default")
      (node (ref "R7-2") (pin "1") (pinfunction "1_1") (pintype "passive"))
      (node (ref "R7-3") (pin "2") (pinfunction "2_2") (pintype "passive"))
      (node (ref "U7") (pin "7") (pinfunction "OUT_7") (pintype "output"))
    )
    (net (code "86") (name "VCC") (class "Default")
      (node (ref "C-S5") (pin "2") (pinfunction "2_2") (pintype "passive"))
      (node (ref "C-S6") (pin "2") (pinfunction "2_2") (pintype "passive"))
      (node (ref "C-S7") (pin "2") (pinfunction "2_2") (pintype "passive"))
      (node (ref "C-S8") (pin "2") (pinfunction "2_2") (pintype "passive"))
      (node (ref "E2") (pin "1") (pinfunction "P_1") (pintype "passive"))
      (node (ref "R-VR1") (pin "2") (pinfunction "2_2") (pintype "passive"))
      (node (ref "R9") (pin "2") (pinfunction "2_2") (pintype "passive"))
      (node (ref "U$1") (pin "P$3") (pinfunction "5V_P$3") (pintype "bidirectional"))
      (node (ref "U$2") (pin "18") (pinfunction "VDD_18") (pintype "power_in"))
      (node (ref "U1") (pin "8") (pinfunction "V+_8") (pintype "power_in"))
      (node (ref "U2") (pin "8") (pinfunction "V+_8") (pintype "power_in"))
      (node (ref "U3") (pin "8") (pinfunction "V+_8") (pintype "power_in"))
      (node (ref "U4") (pin "8") (pinfunction "V+_8") (pintype "power_in"))
      (node (ref "U5") (pin "8") (pinfunction "V+_8") (pintype "power_in"))
      (node (ref "U6") (pin "8") (pinfunction "V+_8") (pintype "power_in"))
      (node (ref "U7") (pin "8") (pinfunction "V+_8") (pintype "power_in"))
      (node (ref "U8") (pin "3") (pinfunction "VCC_3") (pintype "bidirectional"))
    )
    (net (code "87") (name "VFF") (class "Default")
      (node (ref "AC1") (pin "2") (pinfunction "S_2") (pintype "passive"))
      (node (ref "AC2") (pin "2") (pinfunction "S_2") (pintype "passive"))
      (node (ref "AC3") (pin "2") (pinfunction "S_2") (pintype "passive"))
      (node (ref "AC4") (pin "2") (pinfunction "S_2") (pintype "passive"))
      (node (ref "AC5") (pin "2") (pinfunction "S_2") (pintype "passive"))
      (node (ref "AC6") (pin "2") (pinfunction "S_2") (pintype "passive"))
      (node (ref "AC7") (pin "2") (pinfunction "S_2") (pintype "passive"))
      (node (ref "C-VR1") (pin "2") (pinfunction "2_2") (pintype "passive"))
      (node (ref "R-VR1") (pin "1") (pinfunction "1_1") (pintype "passive"))
      (node (ref "R1-5") (pin "2") (pinfunction "2_2") (pintype "passive"))
      (node (ref "R2-5") (pin "2") (pinfunction "2_2") (pintype "passive"))
      (node (ref "R3-5") (pin "2") (pinfunction "2_2") (pintype "passive"))
      (node (ref "R4-5") (pin "2") (pinfunction "2_2") (pintype "passive"))
      (node (ref "R5-5") (pin "2") (pinfunction "2_2") (pintype "passive"))
      (node (ref "R6-5") (pin "2") (pinfunction "2_2") (pintype "passive"))
      (node (ref "R7-5") (pin "2") (pinfunction "2_2") (pintype "passive"))
      (node (ref "RP1") (pin "E") (pinfunction "E_E") (pintype "passive"))
      (node (ref "RP2") (pin "E") (pinfunction "E_E") (pintype "passive"))
      (node (ref "RP3") (pin "E") (pinfunction "E_E") (pintype "passive"))
      (node (ref "RP4") (pin "E") (pinfunction "E_E") (pintype "passive"))
      (node (ref "RP5") (pin "E") (pinfunction "E_E") (pintype "passive"))
      (node (ref "RP6") (pin "E") (pinfunction "E_E") (pintype "passive"))
      (node (ref "RP7") (pin "E") (pinfunction "E_E") (pintype "passive"))
      (node (ref "TL1") (pin "1") (pinfunction "CATHODE_1") (pintype "bidirectional"))
      (node (ref "TL1") (pin "2") (pinfunction "REF_2") (pintype "bidirectional"))
    )
    (net (code "88") (name "unconnected-(U$1-3.3-PadP$1)") (class "Default")
      (node (ref "U$1") (pin "P$1") (pinfunction "3.3_P$1") (pintype "bidirectional"))
    )
    (net (code "89") (name "unconnected-(U$1-A8-PadP$16)") (class "Default")
      (node (ref "U$1") (pin "P$16") (pinfunction "A8_P$16") (pintype "bidirectional"))
    )
    (net (code "90") (name "unconnected-(U$1-A10-PadP$14)") (class "Default")
      (node (ref "U$1") (pin "P$14") (pinfunction "A10_P$14") (pintype "bidirectional"))
    )
    (net (code "91") (name "unconnected-(U$1-A11-PadP$13)") (class "Default")
      (node (ref "U$1") (pin "P$13") (pinfunction "A11_P$13") (pintype "bidirectional"))
    )
    (net (code "92") (name "unconnected-(U$1-A12-PadP$12)") (class "Default")
      (node (ref "U$1") (pin "P$12") (pinfunction "A12_P$12") (pintype "bidirectional"))
    )
    (net (code "93") (name "unconnected-(U$1-A15-PadP$11)") (class "Default")
      (node (ref "U$1") (pin "P$11") (pinfunction "A15_P$11") (pintype "bidirectional"))
    )
    (net (code "94") (name "unconnected-(U$1-B3-PadP$10)") (class "Default")
      (node (ref "U$1") (pin "P$10") (pinfunction "B3_P$10") (pintype "bidirectional"))
    )
    (net (code "95") (name "unconnected-(U$1-B4-PadP$9)") (class "Default")
      (node (ref "U$1") (pin "P$9") (pinfunction "B4_P$9") (pintype "bidirectional"))
    )
    (net (code "96") (name "unconnected-(U$1-B5-PadP$8)") (class "Default")
      (node (ref "U$1") (pin "P$8") (pinfunction "B5_P$8") (pintype "bidirectional"))
    )
    (net (code "97") (name "unconnected-(U$1-B6-PadP$7)") (class "Default")
      (node (ref "U$1") (pin "P$7") (pinfunction "B6_P$7") (pintype "bidirectional"))
    )
    (net (code "98") (name "unconnected-(U$1-B7-PadP$6)") (class "Default")
      (node (ref "U$1") (pin "P$6") (pinfunction "B7_P$6") (pintype "bidirectional"))
    )
    (net (code "99") (name "unconnected-(U$1-B11-PadP$25)") (class "Default")
      (node (ref "U$1") (pin "P$25") (pinfunction "B11_P$25") (pintype "bidirectional"))
    )
    (net (code "100") (name "unconnected-(U$1-G2-PadP$21)") (class "Default")
      (node (ref "U$1") (pin "P$21") (pinfunction "G2_P$21") (pintype "bidirectional"))
    )
    (net (code "101") (name "unconnected-(U$1-G3-PadP$22)") (class "Default")
      (node (ref "U$1") (pin "P$22") (pinfunction "G3_P$22") (pintype "bidirectional"))
    )
    (net (code "102") (name "unconnected-(U$1-N3.3-PadP$23)") (class "Default")
      (node (ref "U$1") (pin "P$23") (pinfunction "N3.3_P$23") (pintype "bidirectional"))
    )
    (net (code "103") (name "unconnected-(U$1-R-PadP$24)") (class "Default")
      (node (ref "U$1") (pin "P$24") (pinfunction "R_P$24") (pintype "bidirectional"))
    )
    (net (code "104") (name "unconnected-(U$1-VB-PadP$40)") (class "Default")
      (node (ref "U$1") (pin "P$40") (pinfunction "VB_P$40") (pintype "bidirectional"))
    )
    (net (code "105") (name "unconnected-(U$2-CLKOUT{slash}SOF-Pad3)") (class "Default")
      (node (ref "U$2") (pin "3") (pinfunction "CLKOUT/SOF_3") (pintype "output"))
    )
    (net (code "106") (name "unconnected-(U$2-~{RX0BF}-Pad11)") (class "Default")
      (node (ref "U$2") (pin "11") (pinfunction "~{RX0BF}_11") (pintype "output"))
    )
    (net (code "107") (name "unconnected-(U$2-~{RX1BF}-Pad10)") (class "Default")
      (node (ref "U$2") (pin "10") (pinfunction "~{RX1BF}_10") (pintype "output"))
    )
    (net (code "108") (name "unconnected-(U$2-~{TX0RTS}-Pad4)") (class "Default")
      (node (ref "U$2") (pin "4") (pinfunction "~{TX0RTS}_4") (pintype "input"))
    )
    (net (code "109") (name "unconnected-(U$2-~{TX1RTS}-Pad5)") (class "Default")
      (node (ref "U$2") (pin "5") (pinfunction "~{TX1RTS}_5") (pintype "input"))
    )
    (net (code "110") (name "unconnected-(U$2-~{TX2RTS}-Pad6)") (class "Default")
      (node (ref "U$2") (pin "6") (pinfunction "~{TX2RTS}_6") (pintype "input"))
    )
    (net (code "111") (name "unconnected-(U8-VREF-Pad5)") (class "Default")
      (node (ref "U8") (pin "5") (pinfunction "VREF_5") (pintype "passive"))
    )
  )
)
